# acrostar_hv_boost.net
KiCad netlist of a schematic drawn in Altium Designer
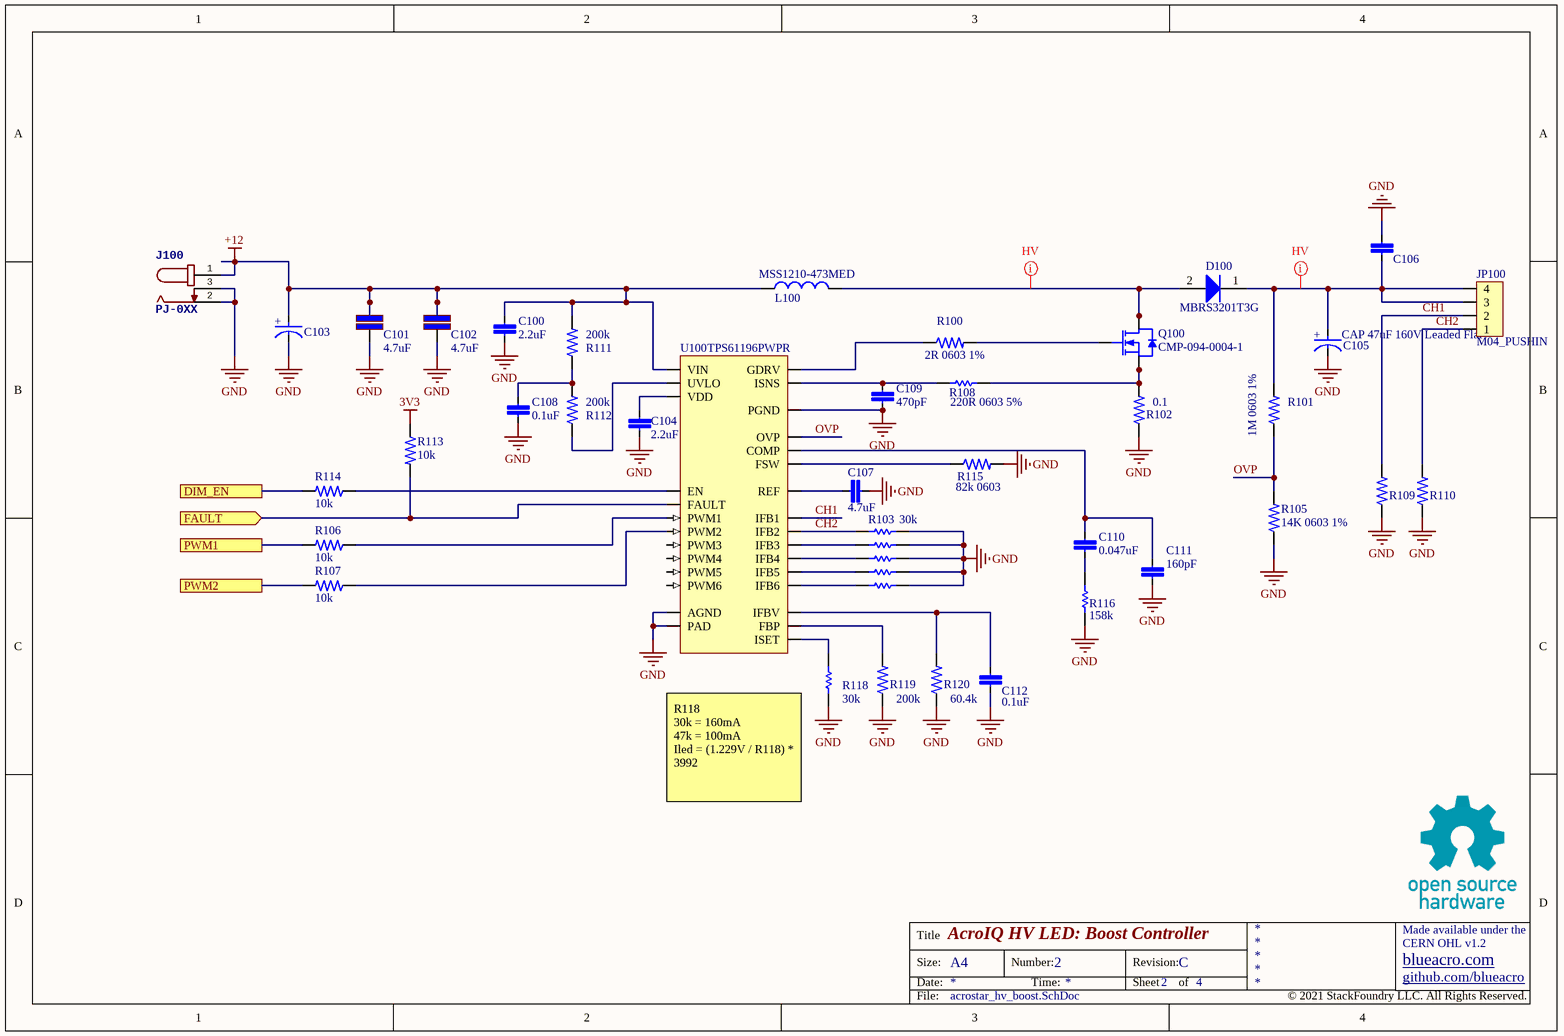
[diagram p0: acrostar_hv_boost.SchDoc]

(export (version "E")
  (design (tool "Eeschema 10.0.6"))
  (components
    (comp (ref "C100")
      (value "2.2uF")
      (footprint "FP-CL10-IPC_B")
      (description "KEMET - C0603C225K4PACTU - CAP, MLCC, X5R, 2.2UF, 16V, 0603")
      (libsource (lib "") (part "C-EU_1"))
    )
    (comp (ref "C101")
      (value "4.7uF")
      (footprint "CAPC3225X20N")
      (description "CAP CER 4.7UF 50V X7R 1210")
      (fields (field (name "TOLERANCE") "10%") (field (name "VOLTAGE") "50V"))
      (libsource (lib "StackFoundry LLC") (part "4.7uF"))
    )
    (comp (ref "C102")
      (value "4.7uF")
      (footprint "CAPC3225X20N")
      (description "CAP CER 4.7UF 50V X7R 1210")
      (fields (field (name "TOLERANCE") "10%") (field (name "VOLTAGE") "50V"))
      (libsource (lib "StackFoundry LLC") (part "4.7uF"))
    )
    (comp (ref "C103")
      (value "CAP 100uF 25V POLY")
      (footprint "25SVF100M-Footprint-1")
      (description "CAP ALUM POLY 100UF 20% 25V SMD")
      (libsource (lib "StackFoundry LLC") (part "CPOL"))
    )
    (comp (ref "C104")
      (value "2.2uF")
      (footprint "FP-CL10-IPC_B")
      (description "KEMET - C0603C225K4PACTU - CAP, MLCC, X5R, 2.2UF, 16V, 0603")
      (libsource (lib "") (part "C-EU_1"))
    )
    (comp (ref "C105")
      (value "CAP 47uF 160V Leaded Flat")
      (footprint "CAP 47uF 160V Leaded Flat-Footprint-1")
      (description "Aluminum Electrolytic Capacitors - Leaded 47uF 160V 85c 12.5x20")
      (libsource (lib "StackFoundry LLC") (part "CPOL"))
    )
    (comp (ref "C106")
      (value "1uF 250V X7R 2220")
      (footprint "CAPC5750X23N")
      (libsource (lib "") (part "C-EU_1"))
    )
    (comp (ref "C107")
      (value "4.7uF")
      (footprint "FP-CL10-IPC_C")
      (description "Cap Ceramic 4.7uF 6.3V X7R 10% SMD 0603 125°C Paper T/R")
      (libsource (lib "") (part "C-EU_2"))
    )
    (comp (ref "C108")
      (value "0.1uF")
      (footprint "FP-CL10-IPC_B")
      (description "Cap Ceramic 0.1uF 50V X7R 20% SMD 0603 125C Paper T/R")
      (libsource (lib "StackFoundry LLC") (part "C-EU"))
    )
    (comp (ref "C109")
      (value "470pF")
      (footprint "FP-CL10-IPC_A")
      (libsource (lib "StackFoundry LLC") (part "C-EU"))
    )
    (comp (ref "C110")
      (value "0.047uF")
      (footprint "FP-CL10-IPC_A")
      (libsource (lib "StackFoundry LLC") (part "C-EU"))
    )
    (comp (ref "C111")
      (value "160pF")
      (footprint "FP-CL10-IPC_A")
      (description "CAP CER 160PF 50V C0G/NP0 0603")
      (libsource (lib "StackFoundry LLC") (part "C-EU"))
    )
    (comp (ref "C112")
      (value "0.1uF")
      (footprint "FP-CL10-IPC_B")
      (description "Cap Ceramic 0.1uF 50V X7R 20% SMD 0603 125C Paper T/R")
      (libsource (lib "StackFoundry LLC") (part "C-EU"))
    )
    (comp (ref "D100")
      (value "MBRS3201T3G")
      (footprint "ONSC-SMC-2-403-03_V")
      (libsource (lib "StackFoundry LLC") (part "ONSC-D-K1A2-2"))
    )
    (comp (ref "J100")
      (value "PJ-0XX")
      (footprint "PJ-036AH")
      (libsource (lib "StackFoundry LLC") (part "Symbol"))
    )
    (comp (ref "JP100")
      (value "M04_PUSHIN")
      (footprint "PHOENIX_PTSM_4_1778780")
      (libsource (lib "StackFoundry LLC") (part "M04_PUSHIN"))
    )
    (comp (ref "L100")
      (value "MSS1210-473MED")
      (footprint "MSS1210-473MED-Footprint-1")
      (description "COILCRAFT   MSS1210-473MED   INDUCTOR, PWR, 47UH, 4.6A, 20%, 6MHZ")
      (libsource (lib "StackFoundry LLC") (part "MSS1210-473MED"))
    )
    (comp (ref "Q100")
      (value "CMP-094-0004-1")
      (footprint "PG-TDSON-8")
      (libsource (lib "StackFoundry LLC") (part "NFET_3S_5D"))
    )
    (comp (ref "R100")
      (value "2R 0603 1%")
      (footprint "RESC1608-IPC-NL")
      (description "RES SMD 2 OHM 1% 1/10W 0603")
      (libsource (lib "StackFoundry LLC") (part "R-US"))
    )
    (comp (ref "R101")
      (value "1M 0603 1%")
      (footprint "RESC1608-IPC-NL")
      (description "VISHAY - CRCW06031M00FKEAHP - RES, AEC-Q200, THICK FILM, 1M, 0603")
      (libsource (lib "StackFoundry LLC") (part "R-US"))
    )
    (comp (ref "R102")
      (value "0.1")
      (footprint "RESC3016X07N")
      (description "Res Thick Film 1206 0.1 Ohm 1% 0.25W(1/4W) ±600ppm/C Molded SMD Paper T/R")
      (libsource (lib "StackFoundry LLC") (part "R-US"))
    )
    (comp (ref "R103")
      (value "30k")
      (footprint "RESC1608-IPC-NL")
      (description "YAGEO - RC0603FR-0730KL - RES, THICK FILM, 30K, 1%, 0.1W, 0603, REEL")
      (fields (field (name "TOLERANCE") "1%"))
      (libsource (lib "StackFoundry LLC") (part "30K 1% 0603"))
    )
    (comp (ref "R104")
      (value "30k")
      (footprint "RESC1608-IPC-NL")
      (description "YAGEO - RC0603FR-0730KL - RES, THICK FILM, 30K, 1%, 0.1W, 0603, REEL")
      (fields (field (name "TOLERANCE") "1%"))
      (libsource (lib "StackFoundry LLC") (part "30K 1% 0603"))
    )
    (comp (ref "R105")
      (value "14K 0603 1%")
      (footprint "RESC1608-IPC-NL")
      (description "Res Thick Film 0603 14K Ohm 1% 1/10W 100ppm/C Molded SMD SMD Punched Carrier T/R")
      (libsource (lib "StackFoundry LLC") (part "R-US"))
    )
    (comp (ref "R106")
      (value "10k")
      (footprint "RESC1608-IPC-NL")
      (description "Res General Purpose Thick Film 0603 10K Ohm 1% 1/10W ±100ppm/°C Molded SMD Paper T/R")
      (libsource (lib "StackFoundry LLC") (part "R-US"))
    )
    (comp (ref "R107")
      (value "10k")
      (footprint "RESC1608-IPC-NL")
      (description "Res General Purpose Thick Film 0603 10K Ohm 1% 1/10W ±100ppm/°C Molded SMD Paper T/R")
      (libsource (lib "StackFoundry LLC") (part "R-US"))
    )
    (comp (ref "R108")
      (value "220R 0603 5%")
      (footprint "RESC1608-IPC-NL")
      (fields (field (name "TOLERANCE") "5%"))
      (libsource (lib "StackFoundry LLC") (part "RES-2"))
    )
    (comp (ref "R109")
      (value "10M 0603")
      (footprint "RESC1608-IPC-NL")
      (description "Res Thick Film 0603 10M Ohm 5% 1/10W ±100ppm/°C Molded SMD SMD Paper T/R")
      (libsource (lib "StackFoundry LLC") (part "R-US"))
    )
    (comp (ref "R110")
      (value "10M 0603")
      (footprint "RESC1608-IPC-NL")
      (description "Res Thick Film 0603 10M Ohm 5% 1/10W ±100ppm/°C Molded SMD SMD Paper T/R")
      (libsource (lib "StackFoundry LLC") (part "R-US"))
    )
    (comp (ref "R111")
      (value "200k")
      (footprint "RESC1608-IPC-NL")
      (description "Thick Film Resistors - SMD 200K OHM 5%")
      (libsource (lib "StackFoundry LLC") (part "R-US"))
    )
    (comp (ref "R112")
      (value "200k")
      (footprint "RESC1608-IPC-NL")
      (description "Thick Film Resistors - SMD 200K OHM 5%")
      (libsource (lib "StackFoundry LLC") (part "R-US"))
    )
    (comp (ref "R113")
      (value "10k")
      (footprint "RESC1608-IPC-NL")
      (description "Res General Purpose Thick Film 0603 10K Ohm 1% 1/10W ±100ppm/°C Molded SMD Paper T/R")
      (libsource (lib "StackFoundry LLC") (part "R-US"))
    )
    (comp (ref "R114")
      (value "10k")
      (footprint "RESC1608-IPC-NL")
      (description "Res General Purpose Thick Film 0603 10K Ohm 1% 1/10W ±100ppm/°C Molded SMD Paper T/R")
      (libsource (lib "StackFoundry LLC") (part "R-US"))
    )
    (comp (ref "R115")
      (value "82k 0603")
      (footprint "RESC1608-IPC-LL")
      (description "RES SMD 82K OHM 1% 1/10W 0603")
      (libsource (lib "StackFoundry LLC") (part "R-US"))
    )
    (comp (ref "R116")
      (value "158k")
      (footprint "RESC1608-IPC-ML")
      (description "Res Thick Film 0603 158K Ohm 1% 0.1W(1/10W) ±100ppm/°C Pad SMD T/R")
      (fields (field (name "TOLERANCE") "1%"))
      (libsource (lib "StackFoundry LLC") (part "RES"))
    )
    (comp (ref "R118")
      (value "30k")
      (footprint "RESC1608-IPC-NL")
      (description "YAGEO - RC0603FR-0730KL - RES, THICK FILM, 30K, 1%, 0.1W, 0603, REEL")
      (fields (field (name "TOLERANCE") "1%"))
      (libsource (lib "StackFoundry LLC") (part "30K 1% 0603"))
    )
    (comp (ref "R119")
      (value "200k")
      (footprint "RESC1608-IPC-NL")
      (description "Thick Film Resistors - SMD 200K OHM 5%")
      (libsource (lib "StackFoundry LLC") (part "R-US"))
    )
    (comp (ref "R120")
      (value "60.4k")
      (footprint "RESC1608-IPC-NL")
      (description "Res Thick Film 0603 60.4K Ohm 1% 0.1W(1/10W) ±100ppm/C Epoxy SMD T/R")
      (libsource (lib "StackFoundry LLC") (part "R-US"))
    )
    (comp (ref "R121")
      (value "30k")
      (footprint "RESC1608-IPC-NL")
      (description "YAGEO - RC0603FR-0730KL - RES, THICK FILM, 30K, 1%, 0.1W, 0603, REEL")
      (fields (field (name "TOLERANCE") "1%"))
      (libsource (lib "StackFoundry LLC") (part "30K 1% 0603"))
    )
    (comp (ref "R122")
      (value "30k")
      (footprint "RESC1608-IPC-NL")
      (description "YAGEO - RC0603FR-0730KL - RES, THICK FILM, 30K, 1%, 0.1W, 0603, REEL")
      (fields (field (name "TOLERANCE") "1%"))
      (libsource (lib "StackFoundry LLC") (part "30K 1% 0603"))
    )
    (comp (ref "R123")
      (value "30k")
      (footprint "RESC1608-IPC-NL")
      (description "YAGEO - RC0603FR-0730KL - RES, THICK FILM, 30K, 1%, 0.1W, 0603, REEL")
      (fields (field (name "TOLERANCE") "1%"))
      (libsource (lib "StackFoundry LLC") (part "30K 1% 0603"))
    )
    (comp (ref "U100")
      (value "TPS61196PWPR")
      (footprint "TSOP65P640X120_HS-29N")
      (description "LED DRVR 9V/12V/15V/18V/24V 28-Pin HTSSOP EP T/R")
      (libsource (lib "StackFoundry LLC") (part "TPS61196PWPR-Symbol-1"))
    )
  )
  (nets
    (net (code "1") (name "+12") (class "Default")
      (node (ref "C100") (pin "2") (pinfunction "2_2") (pintype "passive"))
      (node (ref "C101") (pin "2") (pintype "passive"))
      (node (ref "C102") (pin "2") (pintype "passive"))
      (node (ref "C103") (pin "2") (pinfunction "A_2") (pintype "passive"))
      (node (ref "J100") (pin "1") (pinfunction "1_1") (pintype "passive"))
      (node (ref "L100") (pin "1") (pinfunction "1_1") (pintype "passive"))
      (node (ref "R111") (pin "2") (pinfunction "2_2") (pintype "passive"))
      (node (ref "U100") (pin "28") (pinfunction "VIN_28") (pintype "power_in"))
    )
    (net (code "2") (name "/CH1") (class "Default")
      (node (ref "JP100") (pin "2") (pinfunction "2_2") (pintype "passive"))
      (node (ref "R109") (pin "2") (pinfunction "2_2") (pintype "passive"))
      (node (ref "U100") (pin "12") (pinfunction "IFB1_12") (pintype "passive"))
    )
    (net (code "3") (name "/CH2") (class "Default")
      (node (ref "JP100") (pin "1") (pinfunction "1_1") (pintype "passive"))
      (node (ref "R103") (pin "2") (pinfunction "2_2") (pintype "passive"))
      (node (ref "R110") (pin "2") (pinfunction "2_2") (pintype "passive"))
      (node (ref "U100") (pin "13") (pinfunction "IFB2_13") (pintype "passive"))
    )
    (net (code "4") (name "/DIM_EN") (class "Default")
      (node (ref "R114") (pin "2") (pinfunction "2_2") (pintype "passive"))
    )
    (net (code "5") (name "/FAULT") (class "Default")
      (node (ref "R113") (pin "2") (pinfunction "2_2") (pintype "passive"))
      (node (ref "U100") (pin "27") (pinfunction "FAULT_27") (pintype "passive"))
    )
    (net (code "6") (name "/OVP") (class "Default")
      (node (ref "R101") (pin "1") (pinfunction "1_1") (pintype "passive"))
      (node (ref "R105") (pin "2") (pinfunction "2_2") (pintype "passive"))
      (node (ref "U100") (pin "19") (pinfunction "OVP_19") (pintype "passive"))
    )
    (net (code "7") (name "/PWM1") (class "Default")
      (node (ref "R106") (pin "2") (pinfunction "2_2") (pintype "passive"))
    )
    (net (code "8") (name "/PWM2") (class "Default")
      (node (ref "R107") (pin "2") (pinfunction "2_2") (pintype "passive"))
    )
    (net (code "9") (name "3V3") (class "Default")
      (node (ref "R113") (pin "1") (pinfunction "1_1") (pintype "passive"))
    )
    (net (code "10") (name "GND") (class "Default")
      (node (ref "C100") (pin "1") (pinfunction "1_1") (pintype "passive"))
      (node (ref "C101") (pin "1") (pintype "passive"))
      (node (ref "C102") (pin "1") (pintype "passive"))
      (node (ref "C103") (pin "1") (pinfunction "C_1") (pintype "passive"))
      (node (ref "C104") (pin "1") (pinfunction "1_1") (pintype "passive"))
      (node (ref "C105") (pin "1") (pinfunction "C_1") (pintype "passive"))
      (node (ref "C106") (pin "2") (pinfunction "2_2") (pintype "passive"))
      (node (ref "C107") (pin "2") (pinfunction "2_2") (pintype "passive"))
      (node (ref "C108") (pin "2") (pinfunction "2_2") (pintype "passive"))
      (node (ref "C109") (pin "2") (pinfunction "2_2") (pintype "passive"))
      (node (ref "C111") (pin "2") (pinfunction "2_2") (pintype "passive"))
      (node (ref "C112") (pin "2") (pinfunction "2_2") (pintype "passive"))
      (node (ref "J100") (pin "2") (pinfunction "2_2") (pintype "passive"))
      (node (ref "J100") (pin "3") (pinfunction "3_3") (pintype "passive"))
      (node (ref "R102") (pin "1") (pinfunction "1_1") (pintype "passive"))
      (node (ref "R103") (pin "1") (pinfunction "1_1") (pintype "passive"))
      (node (ref "R104") (pin "1") (pinfunction "1_1") (pintype "passive"))
      (node (ref "R105") (pin "1") (pinfunction "1_1") (pintype "passive"))
      (node (ref "R109") (pin "1") (pinfunction "1_1") (pintype "passive"))
      (node (ref "R110") (pin "1") (pinfunction "1_1") (pintype "passive"))
      (node (ref "R115") (pin "2") (pinfunction "2_2") (pintype "passive"))
      (node (ref "R116") (pin "1") (pinfunction "1_1") (pintype "passive"))
      (node (ref "R118") (pin "1") (pinfunction "1_1") (pintype "passive"))
      (node (ref "R119") (pin "1") (pinfunction "1_1") (pintype "passive"))
      (node (ref "R120") (pin "1") (pinfunction "1_1") (pintype "passive"))
      (node (ref "R121") (pin "1") (pinfunction "1_1") (pintype "passive"))
      (node (ref "R122") (pin "1") (pinfunction "1_1") (pintype "passive"))
      (node (ref "R123") (pin "1") (pinfunction "1_1") (pintype "passive"))
      (node (ref "U100") (pin "18") (pinfunction "AGND_18") (pintype "passive"))
      (node (ref "U100") (pin "22") (pinfunction "PGND_22") (pintype "passive"))
      (node (ref "U100") (pin "29") (pinfunction "PAD_29") (pintype "passive"))
    )
    (net (code "11") (name "Net-(C105-A)") (class "Default")
      (node (ref "C105") (pin "2") (pinfunction "A_2") (pintype "passive"))
      (node (ref "C106") (pin "1") (pinfunction "1_1") (pintype "passive"))
      (node (ref "D100") (pin "1") (pinfunction "K_1") (pintype "passive"))
      (node (ref "JP100") (pin "3") (pinfunction "3_3") (pintype "passive"))
      (node (ref "JP100") (pin "4") (pinfunction "4_4") (pintype "passive"))
      (node (ref "R101") (pin "2") (pinfunction "2_2") (pintype "passive"))
    )
    (net (code "12") (name "Net-(C108-Pad1)") (class "Default")
      (node (ref "C108") (pin "1") (pinfunction "1_1") (pintype "passive"))
      (node (ref "R111") (pin "1") (pinfunction "1_1") (pintype "passive"))
      (node (ref "R112") (pin "2") (pinfunction "2_2") (pintype "passive"))
    )
    (net (code "13") (name "Net-(C110-Pad2)") (class "Default")
      (node (ref "C110") (pin "2") (pinfunction "2_2") (pintype "passive"))
      (node (ref "R116") (pin "2") (pinfunction "2_2") (pintype "passive"))
    )
    (net (code "14") (name "Net-(D100-A)") (class "Default")
      (node (ref "D100") (pin "2") (pinfunction "A_2") (pintype "passive"))
      (node (ref "L100") (pin "2") (pinfunction "2_2") (pintype "passive"))
      (node (ref "Q100") (pin "5") (pinfunction "D_5") (pintype "passive"))
      (node (ref "Q100") (pin "6") (pinfunction "D_6") (pintype "passive"))
      (node (ref "Q100") (pin "7") (pinfunction "D_7") (pintype "passive"))
      (node (ref "Q100") (pin "8") (pinfunction "D_8") (pintype "passive"))
      (node (ref "Q100") (pin "PAD") (pinfunction "D_PAD") (pintype "passive"))
    )
    (net (code "15") (name "Net-(Q100-G)") (class "Default")
      (node (ref "Q100") (pin "4") (pinfunction "G_4") (pintype "passive"))
      (node (ref "R100") (pin "2") (pinfunction "2_2") (pintype "passive"))
    )
    (net (code "16") (name "Net-(Q100-S-Pad1)") (class "Default")
      (node (ref "Q100") (pin "1") (pinfunction "S_1") (pintype "passive"))
      (node (ref "Q100") (pin "2") (pinfunction "S_2") (pintype "passive"))
      (node (ref "Q100") (pin "3") (pinfunction "S_3") (pintype "passive"))
      (node (ref "R102") (pin "2") (pinfunction "2_2") (pintype "passive"))
      (node (ref "R108") (pin "2") (pinfunction "2_2") (pintype "passive"))
    )
    (net (code "17") (name "Net-(U100-COMP)") (class "Default")
      (node (ref "C110") (pin "1") (pinfunction "1_1") (pintype "passive"))
      (node (ref "C111") (pin "1") (pinfunction "1_1") (pintype "passive"))
      (node (ref "U100") (pin "20") (pinfunction "COMP_20") (pintype "passive"))
    )
    (net (code "18") (name "Net-(U100-EN)") (class "Default")
      (node (ref "R114") (pin "1") (pinfunction "1_1") (pintype "passive"))
      (node (ref "U100") (pin "2") (pinfunction "EN_2") (pintype "passive"))
    )
    (net (code "19") (name "Net-(U100-FBP)") (class "Default")
      (node (ref "R119") (pin "2") (pinfunction "2_2") (pintype "passive"))
      (node (ref "U100") (pin "9") (pinfunction "FBP_9") (pintype "passive"))
    )
    (net (code "20") (name "Net-(U100-FSW)") (class "Default")
      (node (ref "R115") (pin "1") (pinfunction "1_1") (pintype "passive"))
      (node (ref "U100") (pin "26") (pinfunction "FSW_26") (pintype "passive"))
    )
    (net (code "21") (name "Net-(U100-GDRV)") (class "Default")
      (node (ref "R100") (pin "1") (pinfunction "1_1") (pintype "passive"))
      (node (ref "U100") (pin "24") (pinfunction "GDRV_24") (pintype "passive"))
    )
    (net (code "22") (name "Net-(U100-IFB3)") (class "Default")
      (node (ref "R104") (pin "2") (pinfunction "2_2") (pintype "passive"))
      (node (ref "U100") (pin "14") (pinfunction "IFB3_14") (pintype "passive"))
    )
    (net (code "23") (name "Net-(U100-IFB4)") (class "Default")
      (node (ref "R121") (pin "2") (pinfunction "2_2") (pintype "passive"))
      (node (ref "U100") (pin "15") (pinfunction "IFB4_15") (pintype "passive"))
    )
    (net (code "24") (name "Net-(U100-IFB5)") (class "Default")
      (node (ref "R122") (pin "2") (pinfunction "2_2") (pintype "passive"))
      (node (ref "U100") (pin "16") (pinfunction "IFB5_16") (pintype "passive"))
    )
    (net (code "25") (name "Net-(U100-IFB6)") (class "Default")
      (node (ref "R123") (pin "2") (pinfunction "2_2") (pintype "passive"))
      (node (ref "U100") (pin "17") (pinfunction "IFB6_17") (pintype "passive"))
    )
    (net (code "26") (name "Net-(U100-IFBV)") (class "Default")
      (node (ref "C112") (pin "1") (pinfunction "1_1") (pintype "passive"))
      (node (ref "R120") (pin "2") (pinfunction "2_2") (pintype "passive"))
      (node (ref "U100") (pin "11") (pinfunction "IFBV_11") (pintype "passive"))
    )
    (net (code "27") (name "Net-(U100-ISET)") (class "Default")
      (node (ref "R118") (pin "2") (pinfunction "2_2") (pintype "passive"))
      (node (ref "U100") (pin "10") (pinfunction "ISET_10") (pintype "passive"))
    )
    (net (code "28") (name "Net-(U100-ISNS)") (class "Default")
      (node (ref "C109") (pin "1") (pinfunction "1_1") (pintype "passive"))
      (node (ref "R108") (pin "1") (pinfunction "1_1") (pintype "passive"))
      (node (ref "U100") (pin "23") (pinfunction "ISNS_23") (pintype "passive"))
    )
    (net (code "29") (name "Net-(U100-PWM1)") (class "Default")
      (node (ref "R106") (pin "1") (pinfunction "1_1") (pintype "passive"))
      (node (ref "U100") (pin "3") (pinfunction "PWM1_3") (pintype "input"))
    )
    (net (code "30") (name "Net-(U100-PWM2)") (class "Default")
      (node (ref "R107") (pin "1") (pinfunction "1_1") (pintype "passive"))
      (node (ref "U100") (pin "4") (pinfunction "PWM2_4") (pintype "input"))
    )
    (net (code "31") (name "Net-(U100-REF)") (class "Default")
      (node (ref "C107") (pin "1") (pinfunction "1_1") (pintype "passive"))
      (node (ref "U100") (pin "21") (pinfunction "REF_21") (pintype "passive"))
    )
    (net (code "32") (name "Net-(U100-UVLO)") (class "Default")
      (node (ref "R112") (pin "1") (pinfunction "1_1") (pintype "passive"))
      (node (ref "U100") (pin "1") (pinfunction "UVLO_1") (pintype "passive"))
    )
    (net (code "33") (name "Net-(U100-VDD)") (class "Default")
      (node (ref "C104") (pin "2") (pinfunction "2_2") (pintype "passive"))
      (node (ref "U100") (pin "25") (pinfunction "VDD_25") (pintype "passive"))
    )
    (net (code "34") (name "unconnected-(U100-PWM3-Pad5)") (class "Default")
      (node (ref "U100") (pin "5") (pinfunction "PWM3_5") (pintype "input"))
    )
    (net (code "35") (name "unconnected-(U100-PWM4-Pad6)") (class "Default")
      (node (ref "U100") (pin "6") (pinfunction "PWM4_6") (pintype "input"))
    )
    (net (code "36") (name "unconnected-(U100-PWM5-Pad7)") (class "Default")
      (node (ref "U100") (pin "7") (pinfunction "PWM5_7") (pintype "input"))
    )
    (net (code "37") (name "unconnected-(U100-PWM6-Pad8)") (class "Default")
      (node (ref "U100") (pin "8") (pinfunction "PWM6_8") (pintype "input"))
    )
  )
)
